# Main.net
KiCad netlist of a schematic drawn in Altium Designer
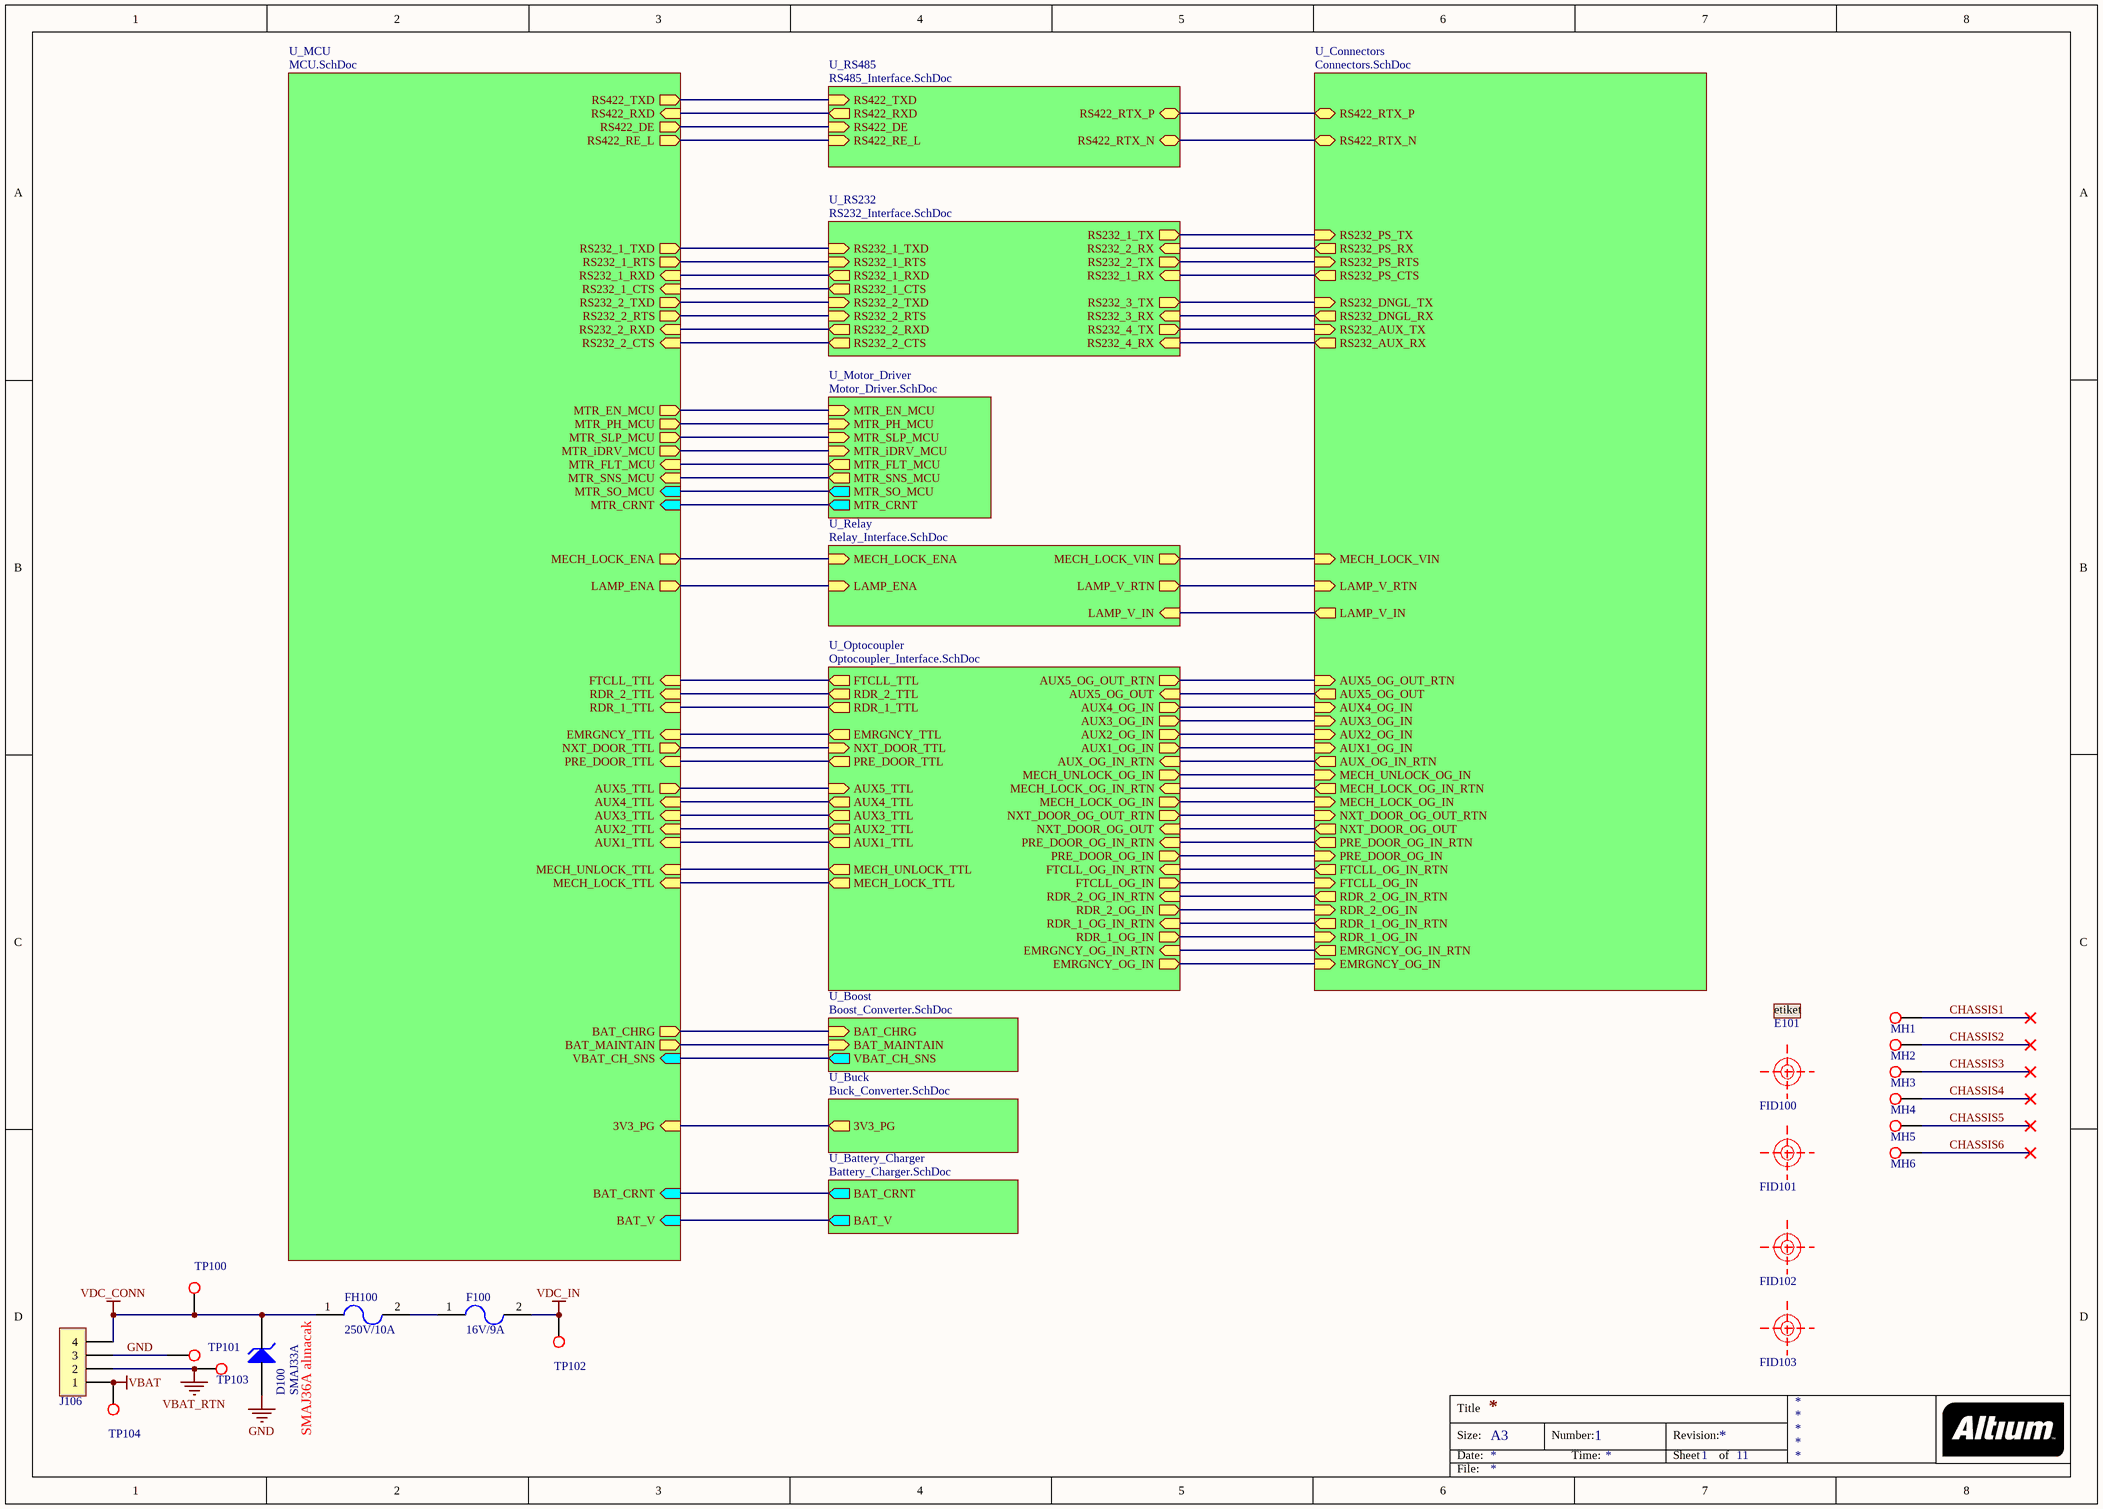
[diagram p0: Main.SchDoc]

(export (version "E")
  (design (tool "Eeschema 10.0.6"))
  (components
    (comp (ref "D100")
      (value "SMAJ33A")
      (footprint "DIOM5226X23N")
      (description "Diode, TVS, 3.5V @35A, 33V, 400W,  Uni-directional, DO-214AC")
      (fields (field (name "MANUFACTURER PART NUMBER") "SMAJ33A-13-F") (field (name "MANUFACTURER") "Diodes"))
      (libsource (lib "Anime_Semiconductor") (part "AS1H-975M-SI60-0001"))
    )
    (comp (ref "E101")
      (value "14x07 mm")
      (footprint "AEME-1407-0000-N000")
      (description "PCB Label, 14x07mm, Non-Conductive")
      (libsource (lib "Anime_Electromechanical") (part "AEME-1407-0000-N000"))
    )
    (comp (ref "F100")
      (value "16V/9A")
      (footprint "AE12-000M-T000-9090")
      (description "Resettable Fuse, 16V, 9A, TH, Radial")
      (fields (field (name "MANUFACTURER") "Littlefuse") (field (name "MANUFACTURER PART NUMBER") "16R900GF"))
      (libsource (lib "Anime_Electromechanical") (part "AE12-000M-T000-9090"))
    )
    (comp (ref "FH100")
      (value "250V/10A")
      (footprint "AE15-000T-0000-0001")
      (description "Fuse block, TH, 5x20mm")
      (fields
        (field (name "MANUFACTURER") "Littlefuse")
        (field (name "MANUFACTURER PART NUMBER") "65600001009")
      )
      (libsource (lib "Anime_Electromechanical") (part "AE15-000T-0000-0001"))
    )
    (comp (ref "FID100")
      (value "Fiducial")
      (footprint "FIDUCIAL_R1MM0")
      (description "Fiducial, Round, 1mm")
      (libsource (lib "Anime_Electromechanical") (part "FIDUCIAL_R1MM0"))
    )
    (comp (ref "FID101")
      (value "Fiducial")
      (footprint "FIDUCIAL_R1MM0")
      (description "Fiducial, Round, 1mm")
      (libsource (lib "Anime_Electromechanical") (part "FIDUCIAL_R1MM0"))
    )
    (comp (ref "FID102")
      (value "Fiducial")
      (footprint "FIDUCIAL_R1MM0")
      (description "Fiducial, Round, 1mm")
      (libsource (lib "Anime_Electromechanical") (part "FIDUCIAL_R1MM0"))
    )
    (comp (ref "FID103")
      (value "Fiducial")
      (footprint "FIDUCIAL_R1MM0")
      (description "Fiducial, Round, 1mm")
      (libsource (lib "Anime_Electromechanical") (part "FIDUCIAL_R1MM0"))
    )
    (comp (ref "J106")
      (value "~")
      (footprint "AJ61-1004-TAPR-RNS0")
      (description "CON, Terminal, Klemens, 4 Pins, 1-Row, 5.08mm, TH, P, R")
      (fields
        (field (name "MANUFACTURER") "ON-SHORE")
        (field (name "MANUFACTURER PART NUMBER") "OSTOQ045451")
      )
      (libsource (lib "Anime_Connector") (part "AJ61-1004-TAPR-RNS0"))
    )
    (comp (ref "MH1")
      (value "AEMT-C00S-1000-0000")
      (footprint "TP100")
      (description "Test Point, Circular, 1mm")
      (libsource (lib "Anime_Electromechanical") (part "AEMT-C00S-1000-0000"))
    )
    (comp (ref "MH2")
      (value "AEMT-C00S-1000-0000")
      (footprint "TP100")
      (description "Test Point, Circular, 1mm")
      (libsource (lib "Anime_Electromechanical") (part "AEMT-C00S-1000-0000"))
    )
    (comp (ref "MH3")
      (value "AEMT-C00S-1000-0000")
      (footprint "TP100")
      (description "Test Point, Circular, 1mm")
      (libsource (lib "Anime_Electromechanical") (part "AEMT-C00S-1000-0000"))
    )
    (comp (ref "MH4")
      (value "AEMT-C00S-1000-0000")
      (footprint "TP100")
      (description "Test Point, Circular, 1mm")
      (libsource (lib "Anime_Electromechanical") (part "AEMT-C00S-1000-0000"))
    )
    (comp (ref "MH5")
      (value "AEMT-C00S-1000-0000")
      (footprint "TP100")
      (description "Test Point, Circular, 1mm")
      (libsource (lib "Anime_Electromechanical") (part "AEMT-C00S-1000-0000"))
    )
    (comp (ref "MH6")
      (value "AEMT-C00S-1000-0000")
      (footprint "TP100")
      (description "Test Point, Circular, 1mm")
      (libsource (lib "Anime_Electromechanical") (part "AEMT-C00S-1000-0000"))
    )
    (comp (ref "TP100")
      (value "AEMT-C00S-1000-0000")
      (footprint "TP100")
      (description "Test Point, Circular, 1mm")
      (libsource (lib "Anime_Electromechanical") (part "AEMT-C00S-1000-0000"))
    )
    (comp (ref "TP101")
      (value "AEMT-C00S-1000-0000")
      (footprint "TP100")
      (description "Test Point, Circular, 1mm")
      (libsource (lib "Anime_Electromechanical") (part "AEMT-C00S-1000-0000"))
    )
    (comp (ref "TP102")
      (value "AEMT-C00S-1000-0000")
      (footprint "TP100")
      (description "Test Point, Circular, 1mm")
      (libsource (lib "Anime_Electromechanical") (part "AEMT-C00S-1000-0000"))
    )
    (comp (ref "TP103")
      (value "AEMT-C00S-1000-0000")
      (footprint "TP100")
      (description "Test Point, Circular, 1mm")
      (libsource (lib "Anime_Electromechanical") (part "AEMT-C00S-1000-0000"))
    )
    (comp (ref "TP104")
      (value "AEMT-C00S-1000-0000")
      (footprint "TP100")
      (description "Test Point, Circular, 1mm")
      (libsource (lib "Anime_Electromechanical") (part "AEMT-C00S-1000-0000"))
    )
  )
  (nets
    (net (code "18") (name "/CHASSIS1") (class "Default")
      (node (ref "MH1") (pin "1") (pintype "passive+no_connect"))
    )
    (net (code "19") (name "/CHASSIS2") (class "Default")
      (node (ref "MH2") (pin "1") (pintype "passive+no_connect"))
    )
    (net (code "20") (name "/CHASSIS3") (class "Default")
      (node (ref "MH3") (pin "1") (pintype "passive+no_connect"))
    )
    (net (code "21") (name "/CHASSIS4") (class "Default")
      (node (ref "MH4") (pin "1") (pintype "passive+no_connect"))
    )
    (net (code "22") (name "/CHASSIS5") (class "Default")
      (node (ref "MH5") (pin "1") (pintype "passive+no_connect"))
    )
    (net (code "23") (name "/CHASSIS6") (class "Default")
      (node (ref "MH6") (pin "1") (pintype "passive+no_connect"))
    )
    (net (code "83") (name "GND") (class "Default")
      (node (ref "D100") (pin "2") (pinfunction "A_2") (pintype "passive"))
      (node (ref "J106") (pin "3") (pinfunction "3_3") (pintype "passive"))
      (node (ref "TP101") (pin "1") (pintype "passive"))
    )
    (net (code "84") (name "Net-(F100-Pad1)") (class "Default")
      (node (ref "F100") (pin "1") (pinfunction "1_1") (pintype "passive"))
      (node (ref "FH100") (pin "2") (pinfunction "2_2") (pintype "passive"))
    )
    (net (code "85") (name "VBAT") (class "Default")
      (node (ref "J106") (pin "1") (pinfunction "1_1") (pintype "passive"))
      (node (ref "TP104") (pin "1") (pintype "passive"))
    )
    (net (code "86") (name "VBAT_RTN") (class "Default")
      (node (ref "J106") (pin "2") (pinfunction "2_2") (pintype "passive"))
      (node (ref "TP103") (pin "1") (pintype "passive"))
    )
    (net (code "87") (name "VDC_CONN") (class "Default")
      (node (ref "D100") (pin "1") (pinfunction "K_1") (pintype "passive"))
      (node (ref "FH100") (pin "1") (pinfunction "1_1") (pintype "passive"))
      (node (ref "J106") (pin "4") (pinfunction "4_4") (pintype "passive"))
      (node (ref "TP100") (pin "1") (pintype "passive"))
    )
    (net (code "88") (name "VDC_IN") (class "Default")
      (node (ref "F100") (pin "2") (pinfunction "2_2") (pintype "passive"))
      (node (ref "TP102") (pin "1") (pintype "passive"))
    )
  )
)
